# 02config.net
KiCad netlist of a schematic drawn in Altium Designer
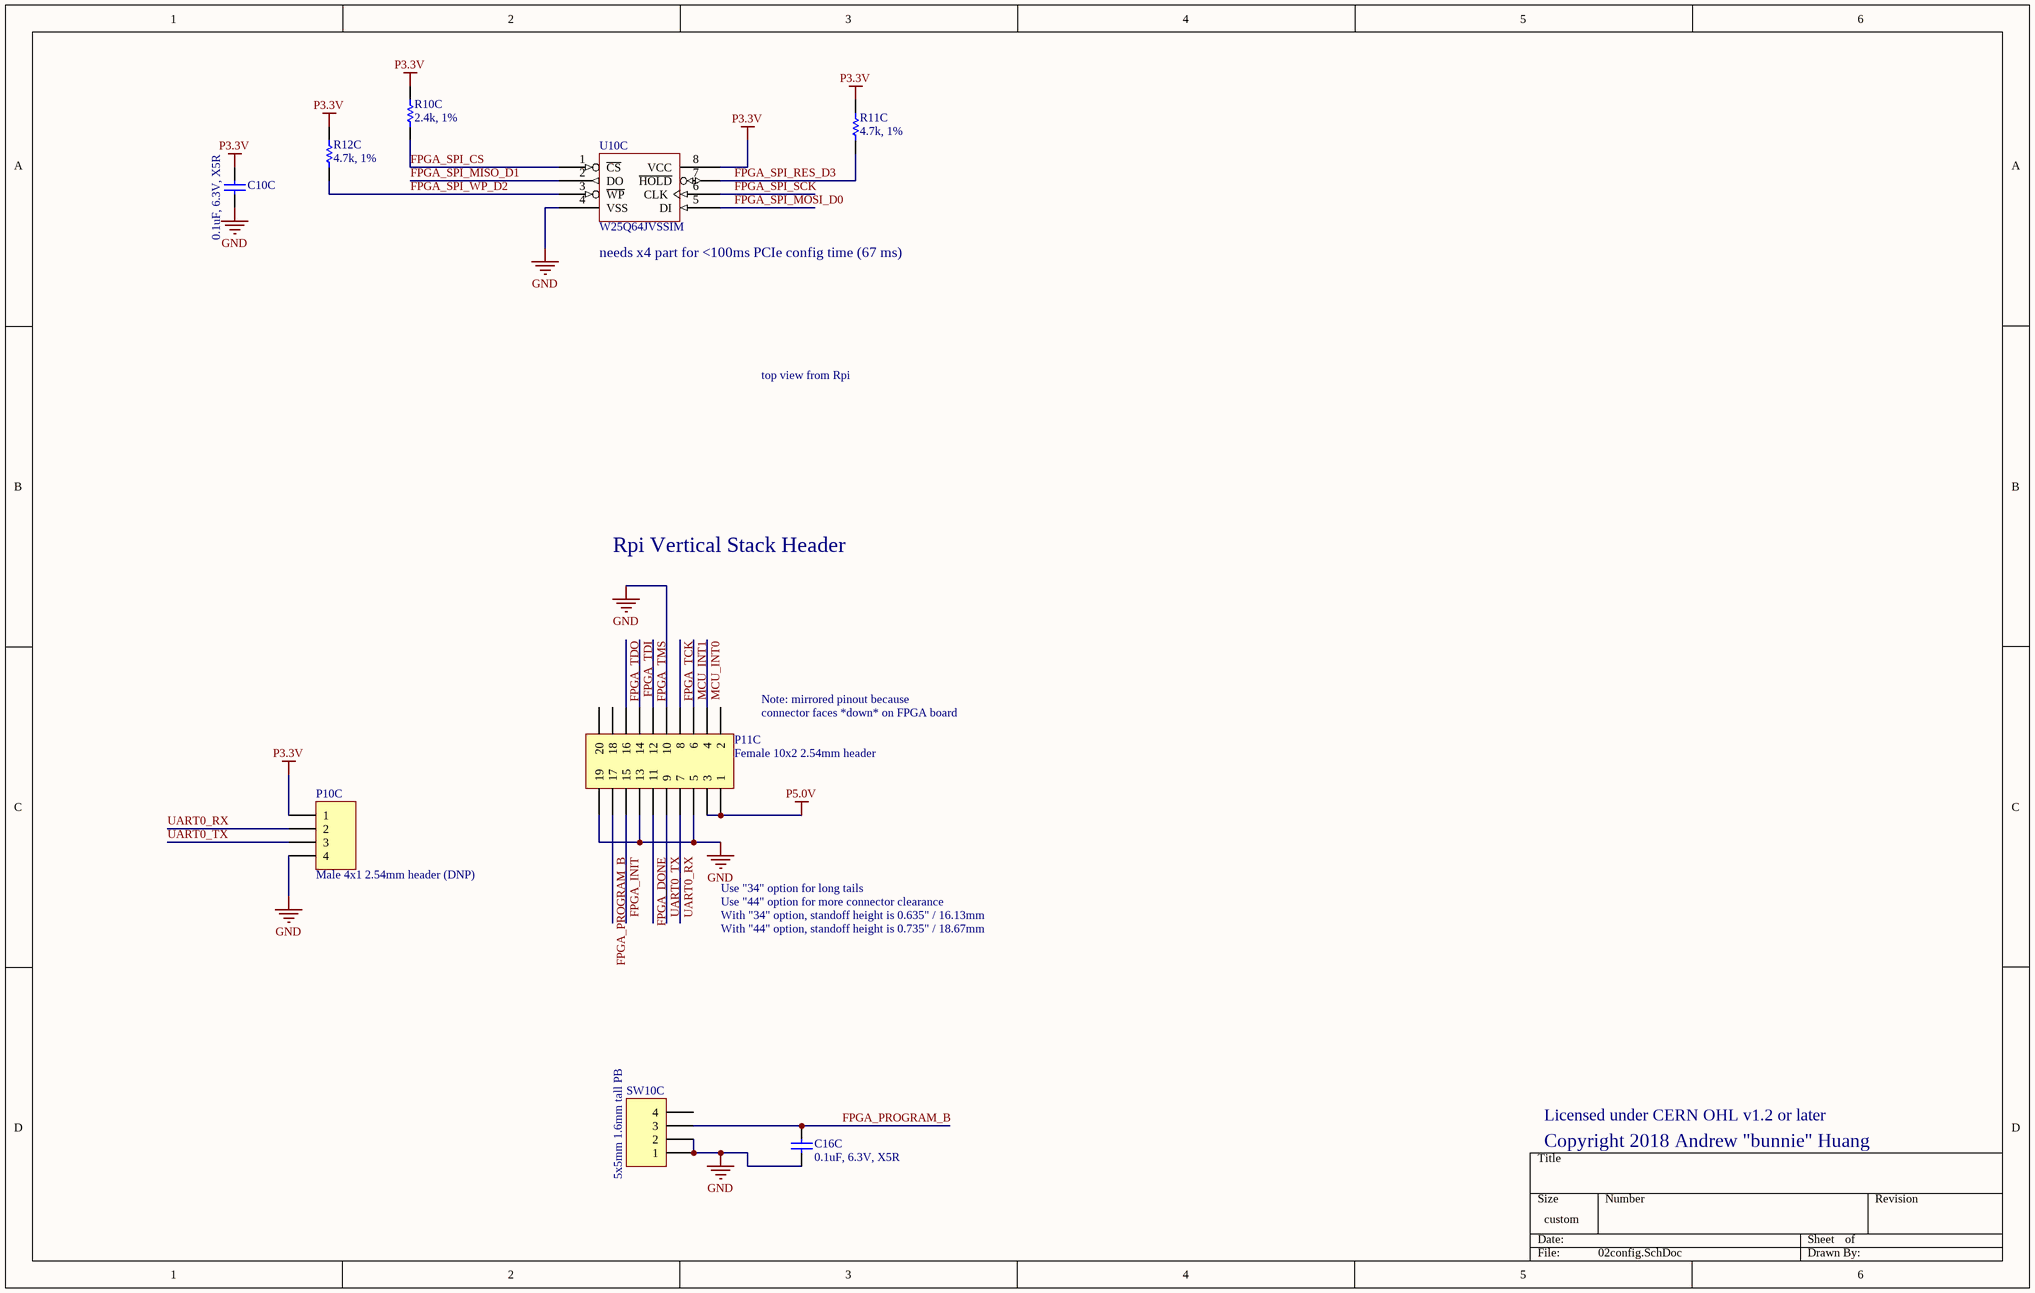
[diagram p0: 02config.SchDoc]

(export (version "E")
  (design (tool "Eeschema 10.0.6"))
  (components
    (comp (ref "C10C")
      (value "0.1uF, 6.3V, X5R")
      (footprint "CAPC0603X03L")
      (description "Capacitor (Semiconductor SIM Model)")
      (fields (field (name "MPN") "CL03A104KQ3NNNC"))
      (libsource (lib "Miscellaneous Devices") (part "Cap Semi"))
    )
    (comp (ref "C16C")
      (value "0.1uF, 6.3V, X5R")
      (footprint "CAPC0603X03L")
      (description "Capacitor (Semiconductor SIM Model)")
      (fields (field (name "MPN") "CL03A104KQ3NNNC"))
      (libsource (lib "Miscellaneous Devices") (part "Cap Semi"))
    )
    (comp (ref "P10C")
      (value "Male 4x1 2.54mm header (DNP)")
      (footprint "HDR1X4")
      (description "Header, 4-Pin")
      (fields (field (name "MPN") "DNP") (field (name "PUBLISHER") "Altium Limited"))
      (libsource (lib "") (part "Header 4_1"))
    )
    (comp (ref "P11C")
      (value "Female 10x2 2.54mm header")
      (footprint "HDR2X10")
      (description "Header, 10-Pin, Dual row")
      (fields (field (name "MPN") "F201-SGP-D048-20-P4") (field (name "PUBLISHER") "Altium Limited"))
      (libsource (lib "Miscellaneous Connectors") (part "Header 10X2"))
    )
    (comp (ref "R10C")
      (value "2.4k, 1%")
      (footprint "CAPC0603X03L")
      (description "Resistor")
      (fields (field (name "MPN") "ANY"))
      (libsource (lib "Miscellaneous Devices") (part "Res1"))
    )
    (comp (ref "R11C")
      (value "4.7k, 1%")
      (footprint "RESC1005N")
      (description "Resistor")
      (fields (field (name "MPN") "RS02U472FT"))
      (libsource (lib "Miscellaneous Devices") (part "Res1"))
    )
    (comp (ref "R12C")
      (value "4.7k, 1%")
      (footprint "RESC1005N")
      (description "Resistor")
      (fields (field (name "MPN") "RS02U472FT"))
      (libsource (lib "Miscellaneous Devices") (part "Res1"))
    )
    (comp (ref "SW10C")
      (value "5x5mm 1.6mm tall PB")
      (footprint "SWITCH_TS-1187A")
      (description "Chi Fung TS-1187A")
      (fields (field (name "MPN") "SW-PB-5X5-1.6") (field (name "PUBLISHER") "Altium Limited"))
      (libsource (lib "Miscellaneous Connectors") (part "Header 4"))
    )
    (comp (ref "U10C")
      (value "W25Q64JVSSIM")
      (footprint "SOIC127P790X216-8N")
      (description "64Mbit SPI NOR FLASH")
      (libsource (lib "commonsch") (part "EN25P05-50GCP"))
    )
  )
  (nets
    (net (code "1") (name "/FPGA_DONE") (class "Default")
      (node (ref "P11C") (pin "11") (pinfunction "11_11") (pintype "passive"))
    )
    (net (code "2") (name "/FPGA_INIT") (class "Default")
      (node (ref "P11C") (pin "15") (pinfunction "15_15") (pintype "passive"))
    )
    (net (code "3") (name "/FPGA_PROGRAM_B") (class "Default")
      (node (ref "C16C") (pin "1") (pinfunction "1_1") (pintype "passive"))
      (node (ref "P11C") (pin "17") (pinfunction "17_17") (pintype "passive"))
      (node (ref "SW10C") (pin "3") (pinfunction "3_3") (pintype "passive"))
    )
    (net (code "4") (name "/FPGA_SPI_CS") (class "Default")
      (node (ref "R10C") (pin "2") (pinfunction "2_2") (pintype "passive"))
      (node (ref "U10C") (pin "1") (pinfunction "~{CS}_1") (pintype "input"))
    )
    (net (code "5") (name "/FPGA_SPI_MISO_D1") (class "Default")
      (node (ref "U10C") (pin "2") (pinfunction "DO_2") (pintype "output"))
    )
    (net (code "6") (name "/FPGA_SPI_MOSI_D0") (class "Default")
      (node (ref "U10C") (pin "5") (pinfunction "DI_5") (pintype "input"))
    )
    (net (code "7") (name "/FPGA_SPI_RES_D3") (class "Default")
      (node (ref "R11C") (pin "2") (pinfunction "2_2") (pintype "passive"))
      (node (ref "U10C") (pin "7") (pinfunction "~{HOLD}_7") (pintype "bidirectional"))
    )
    (net (code "8") (name "/FPGA_SPI_SCK") (class "Default")
      (node (ref "U10C") (pin "6") (pinfunction "CLK_6") (pintype "input"))
    )
    (net (code "9") (name "/FPGA_SPI_WP_D2") (class "Default")
      (node (ref "R12C") (pin "2") (pinfunction "2_2") (pintype "passive"))
      (node (ref "U10C") (pin "3") (pinfunction "~{WP}_3") (pintype "input"))
    )
    (net (code "10") (name "/FPGA_TCK") (class "Default")
      (node (ref "P11C") (pin "8") (pinfunction "8_8") (pintype "passive"))
    )
    (net (code "11") (name "/FPGA_TDI") (class "Default")
      (node (ref "P11C") (pin "14") (pinfunction "14_14") (pintype "passive"))
    )
    (net (code "12") (name "/FPGA_TDO") (class "Default")
      (node (ref "P11C") (pin "16") (pinfunction "16_16") (pintype "passive"))
    )
    (net (code "13") (name "/FPGA_TMS") (class "Default")
      (node (ref "P11C") (pin "12") (pinfunction "12_12") (pintype "passive"))
    )
    (net (code "14") (name "/MCU_INT0") (class "Default")
      (node (ref "P11C") (pin "4") (pinfunction "4_4") (pintype "passive"))
    )
    (net (code "15") (name "/MCU_INT1") (class "Default")
      (node (ref "P11C") (pin "6") (pinfunction "6_6") (pintype "passive"))
    )
    (net (code "16") (name "/UART0_RX") (class "Default")
      (node (ref "P10C") (pin "2") (pinfunction "2_2") (pintype "passive"))
      (node (ref "P11C") (pin "7") (pinfunction "7_7") (pintype "passive"))
    )
    (net (code "17") (name "/UART0_TX") (class "Default")
      (node (ref "P10C") (pin "3") (pinfunction "3_3") (pintype "passive"))
      (node (ref "P11C") (pin "9") (pinfunction "9_9") (pintype "passive"))
    )
    (net (code "18") (name "GND") (class "Default")
      (node (ref "C10C") (pin "2") (pinfunction "2_2") (pintype "passive"))
      (node (ref "C16C") (pin "2") (pinfunction "2_2") (pintype "passive"))
      (node (ref "P10C") (pin "4") (pinfunction "4_4") (pintype "passive"))
      (node (ref "P11C") (pin "10") (pinfunction "10_10") (pintype "passive"))
      (node (ref "P11C") (pin "13") (pinfunction "13_13") (pintype "passive"))
      (node (ref "P11C") (pin "19") (pinfunction "19_19") (pintype "passive"))
      (node (ref "P11C") (pin "5") (pinfunction "5_5") (pintype "passive"))
      (node (ref "SW10C") (pin "1") (pinfunction "1_1") (pintype "passive"))
      (node (ref "SW10C") (pin "2") (pinfunction "2_2") (pintype "passive"))
      (node (ref "U10C") (pin "4") (pinfunction "VSS_4") (pintype "power_in"))
    )
    (net (code "19") (name "P3.3V") (class "Default")
      (node (ref "C10C") (pin "1") (pinfunction "1_1") (pintype "passive"))
      (node (ref "P10C") (pin "1") (pinfunction "1_1") (pintype "passive"))
      (node (ref "R10C") (pin "1") (pinfunction "1_1") (pintype "passive"))
      (node (ref "R11C") (pin "1") (pinfunction "1_1") (pintype "passive"))
      (node (ref "R12C") (pin "1") (pinfunction "1_1") (pintype "passive"))
      (node (ref "U10C") (pin "8") (pinfunction "VCC_8") (pintype "power_in"))
    )
    (net (code "20") (name "P5.0V") (class "Default")
      (node (ref "P11C") (pin "1") (pinfunction "1_1") (pintype "passive"))
      (node (ref "P11C") (pin "3") (pinfunction "3_3") (pintype "passive"))
    )
    (net (code "21") (name "unconnected-(P11C-Pad2)") (class "Default")
      (node (ref "P11C") (pin "2") (pinfunction "2_2") (pintype "passive"))
    )
    (net (code "22") (name "unconnected-(P11C-Pad18)") (class "Default")
      (node (ref "P11C") (pin "18") (pinfunction "18_18") (pintype "passive"))
    )
    (net (code "23") (name "unconnected-(P11C-Pad20)") (class "Default")
      (node (ref "P11C") (pin "20") (pinfunction "20_20") (pintype "passive"))
    )
    (net (code "24") (name "unconnected-(SW10C-Pad4)") (class "Default")
      (node (ref "SW10C") (pin "4") (pinfunction "4_4") (pintype "passive"))
    )
  )
)
